# DIP_Switch.net
KiCad netlist of a schematic drawn in Altium Designer
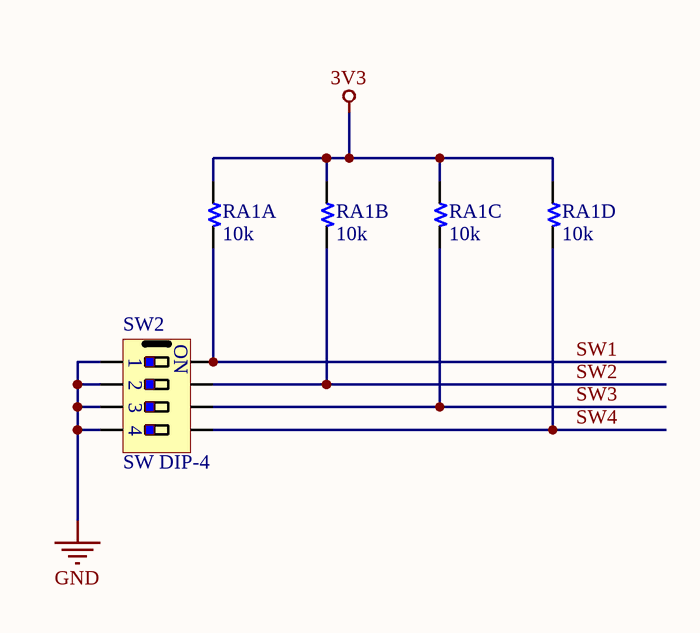
[diagram p0: DIP_Switch.SchDoc]

(export (version "E")
  (design (tool "Eeschema 10.0.6"))
  (components
    (comp (ref "RA1A")
      (value "10k")
      (footprint "R 0805")
      (description "Resistor")
      (libsource (lib "chipfc_libs") (part "Resistor"))
    )
    (comp (ref "RA1B")
      (value "10k")
      (footprint "R 0805")
      (description "Resistor")
      (libsource (lib "chipfc_libs") (part "Resistor"))
    )
    (comp (ref "RA1C")
      (value "10k")
      (footprint "R 0805")
      (description "Resistor")
      (libsource (lib "chipfc_libs") (part "Resistor"))
    )
    (comp (ref "RA1D")
      (value "10k")
      (footprint "R 0805")
      (description "Resistor")
      (libsource (lib "chipfc_libs") (part "Resistor"))
    )
    (comp (ref "SW2")
      (value "SW DIP-4")
      (footprint "SW/DIP4")
      (libsource (lib "chipfc_libs") (part "SW DIP-4"))
    )
  )
  (nets
    (net (code "1") (name "/SW1") (class "Default")
      (node (ref "RA1A") (pin "2") (pinfunction "2_2") (pintype "passive"))
      (node (ref "SW2") (pin "8") (pinfunction "8_8") (pintype "passive"))
    )
    (net (code "2") (name "/SW2") (class "Default")
      (node (ref "RA1B") (pin "2") (pinfunction "2_2") (pintype "passive"))
      (node (ref "SW2") (pin "7") (pinfunction "7_7") (pintype "passive"))
    )
    (net (code "3") (name "/SW3") (class "Default")
      (node (ref "RA1C") (pin "2") (pinfunction "2_2") (pintype "passive"))
      (node (ref "SW2") (pin "6") (pinfunction "6_6") (pintype "passive"))
    )
    (net (code "4") (name "/SW4") (class "Default")
      (node (ref "RA1D") (pin "2") (pinfunction "2_2") (pintype "passive"))
      (node (ref "SW2") (pin "5") (pinfunction "5_5") (pintype "passive"))
    )
    (net (code "5") (name "3V3") (class "Default")
      (node (ref "RA1A") (pin "1") (pinfunction "1_1") (pintype "passive"))
      (node (ref "RA1B") (pin "1") (pinfunction "1_1") (pintype "passive"))
      (node (ref "RA1C") (pin "1") (pinfunction "1_1") (pintype "passive"))
      (node (ref "RA1D") (pin "1") (pinfunction "1_1") (pintype "passive"))
    )
    (net (code "6") (name "GND") (class "Default")
      (node (ref "SW2") (pin "1") (pinfunction "1_1") (pintype "passive"))
      (node (ref "SW2") (pin "2") (pinfunction "2_2") (pintype "passive"))
      (node (ref "SW2") (pin "3") (pinfunction "3_3") (pintype "passive"))
      (node (ref "SW2") (pin "4") (pinfunction "4_4") (pintype "passive"))
    )
  )
)
